# GO-RGO_BOARD_26-09-22_final_update_7PM.net
KiCad netlist of a schematic drawn in EAGLE
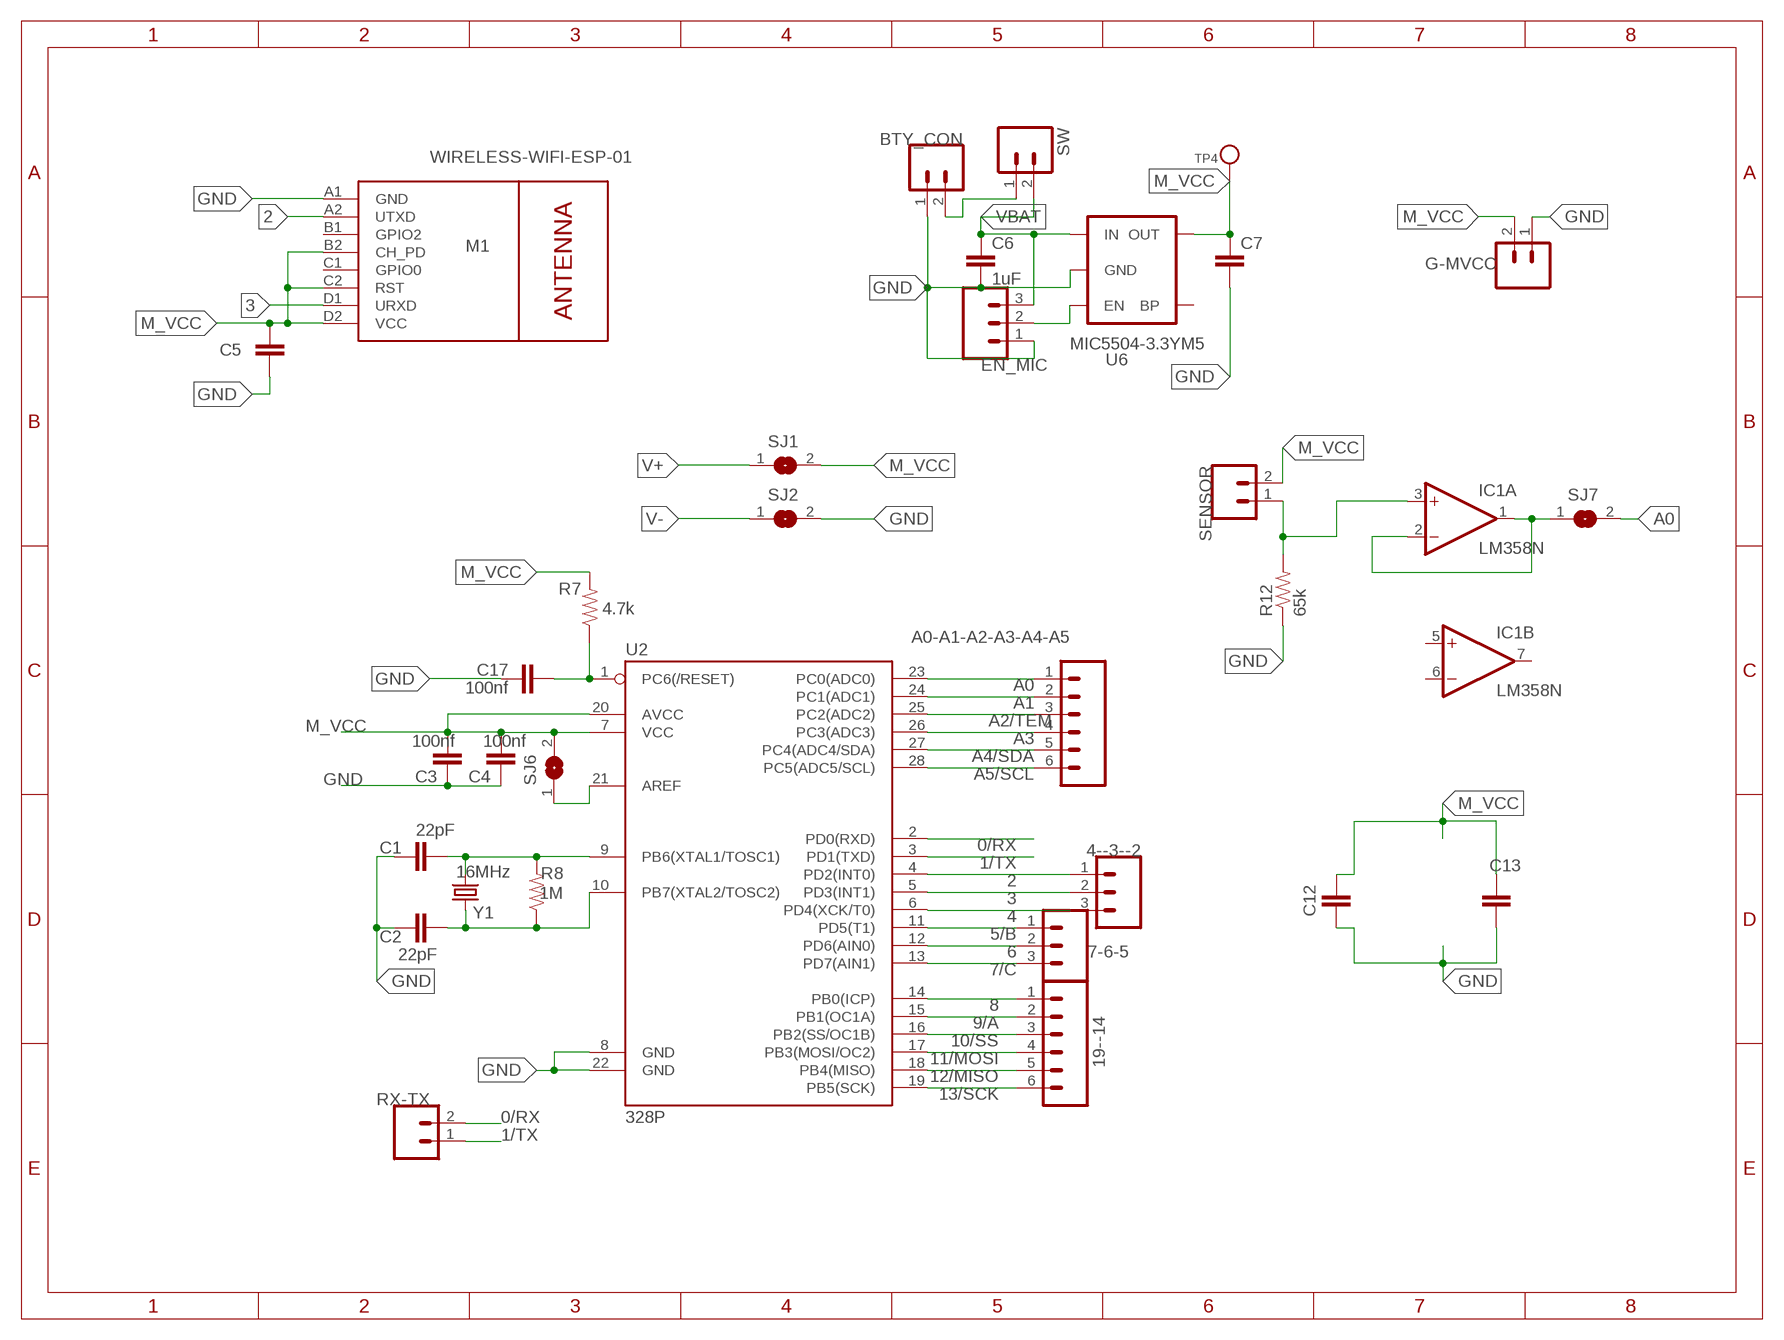
[diagram p0: schematic, sheet 1]

(export (version "E")
  (design (tool "Eeschema 10.0.6"))
  (components
    (comp (ref "4--3--2")
      (value "M03PTH")
      (footprint "eagle-import:1X03")
      (libsource (lib "eagle-import") (part "M03PTH"))
    )
    (comp (ref "7-6-5")
      (value "M03PTH")
      (footprint "eagle-import:1X03")
      (libsource (lib "eagle-import") (part "SparkFun-Connectors1_M03PTH"))
    )
    (comp (ref "19--14")
      (value "M06SIP")
      (footprint "eagle-import:1X06")
      (libsource (lib "eagle-import") (part "M06SIP"))
    )
    (comp (ref "A0-A1-A2-A3-A4-A5")
      (value "M06SIP")
      (footprint "eagle-import:1X06")
      (libsource (lib "eagle-import") (part "M06SIP"))
    )
    (comp (ref "BTY_CON")
      (value "M02PTH")
      (footprint "eagle-import:1X02")
      (libsource (lib "eagle-import") (part "SparkFun-3-2-07_M02PTH"))
    )
    (comp (ref "C1")
      (value "22pF")
      (footprint "eagle-import:0805")
      (libsource (lib "eagle-import") (part "CAP0805"))
    )
    (comp (ref "C2")
      (value "22pF")
      (footprint "eagle-import:0805")
      (libsource (lib "eagle-import") (part "CAP0805"))
    )
    (comp (ref "C3")
      (value "100nf")
      (footprint "eagle-import:0805")
      (libsource (lib "eagle-import") (part "CAP0805"))
    )
    (comp (ref "C4")
      (value "100nf")
      (footprint "eagle-import:0805")
      (libsource (lib "eagle-import") (part "CAP0805"))
    )
    (comp (ref "C5")
      (value "100nf")
      (footprint "eagle-import:0805")
      (libsource (lib "eagle-import") (part "CAP0805"))
    )
    (comp (ref "C6")
      (value "1uF")
      (footprint "eagle-import:0805")
      (libsource (lib "eagle-import") (part "SparkFun-Passives1_CAP0805"))
    )
    (comp (ref "C7")
      (value "1uF")
      (footprint "eagle-import:0805")
      (libsource (lib "eagle-import") (part "SparkFun-Passives1_CAP0805"))
    )
    (comp (ref "C12")
      (value "100nf")
      (footprint "eagle-import:0805")
      (libsource (lib "eagle-import") (part "SparkFun-Passives1_CAP0805"))
    )
    (comp (ref "C13")
      (value "100nf")
      (footprint "eagle-import:0805")
      (libsource (lib "eagle-import") (part "SparkFun-Passives1_CAP0805"))
    )
    (comp (ref "C17")
      (value "100nf")
      (footprint "eagle-import:0805")
      (libsource (lib "eagle-import") (part "CAP0805"))
    )
    (comp (ref "EN_MIC")
      (value "M03PTH")
      (footprint "eagle-import:1X03")
      (libsource (lib "eagle-import") (part "SparkFun-3-2-07_M03PTH"))
    )
    (comp (ref "G-MVCC")
      (value "M02PTH")
      (footprint "eagle-import:1X02")
      (libsource (lib "eagle-import") (part "SparkFun-3-2-07_M02PTH"))
    )
    (comp (ref "IC1")
      (value "LM358N")
      (footprint "eagle-import:DIL08")
      (libsource (lib "eagle-import") (part "LM358N"))
    )
    (comp (ref "M1")
      (value "WIRELESS-WIFI-ESP-01")
      (footprint "eagle-import:WIRELESS-WIFI-ESP-01")
      (libsource (lib "eagle-import") (part "WIRELESS-WIFI-ESP-01"))
    )
    (comp (ref "R7")
      (value "4.7k")
      (footprint "eagle-import:0805")
      (libsource (lib "eagle-import") (part "RESISTOR0805-RES"))
    )
    (comp (ref "R8")
      (value "1M")
      (footprint "eagle-import:0805")
      (libsource (lib "eagle-import") (part "RESISTOR0805-RES"))
    )
    (comp (ref "R12")
      (value "65k")
      (footprint "eagle-import:0805")
      (libsource (lib "eagle-import") (part "RESISTOR0805-RES"))
    )
    (comp (ref "RX-TX")
      (value "M02PTH")
      (footprint "eagle-import:1X02")
      (libsource (lib "eagle-import") (part "SparkFun-3-2-07_M02PTH"))
    )
    (comp (ref "SENSOR")
      (value "M02PTH")
      (footprint "eagle-import:1X02")
      (libsource (lib "eagle-import") (part "SparkFun-3-2-07_M02PTH"))
    )
    (comp (ref "SJ1") (value "SJ") (footprint "eagle-import:SJ") (libsource (lib "eagle-import") (part "SJ")))
    (comp (ref "SJ2") (value "SJ") (footprint "eagle-import:SJ") (libsource (lib "eagle-import") (part "SJ")))
    (comp (ref "SJ6") (value "SJ") (footprint "eagle-import:SJ") (libsource (lib "eagle-import") (part "SJ")))
    (comp (ref "SJ7") (value "SJ") (footprint "eagle-import:SJ") (libsource (lib "eagle-import") (part "SJ")))
    (comp (ref "SW")
      (value "M02PTH")
      (footprint "eagle-import:1X02")
      (libsource (lib "eagle-import") (part "M02PTH"))
    )
    (comp (ref "TP4")
      (value "TESTPOINTROUND1MM")
      (footprint "eagle-import:TESTPOINT_ROUND_1MM")
      (libsource (lib "eagle-import") (part "TESTPOINTROUND1MM"))
    )
    (comp (ref "U2")
      (value "328P")
      (footprint "eagle-import:DIP28")
      (libsource (lib "eagle-import") (part "ATMEGA328P_PDIP"))
    )
    (comp (ref "U6")
      (value "MIC5504-3.3YM5")
      (footprint "eagle-import:SOT23-5")
      (libsource (lib "eagle-import") (part "V_REG_LDOSMD"))
    )
    (comp (ref "Y1")
      (value "16MHz")
      (footprint "eagle-import:HC49US")
      (libsource (lib "eagle-import") (part "CRYSTAL-16MHZPTH-HC49US"))
    )
  )
  (nets
    (net (code "1") (name "/0{slash}RX") (class "Default")
      (node (ref "RX-TX") (pin "2") (pinfunction "2_2") (pintype "passive"))
      (node (ref "U2") (pin "2") (pinfunction "PD0(RXD)_2") (pintype "bidirectional"))
    )
    (net (code "2") (name "/1{slash}TX") (class "Default")
      (node (ref "RX-TX") (pin "1") (pinfunction "1_1") (pintype "passive"))
      (node (ref "U2") (pin "3") (pinfunction "PD1(TXD)_3") (pintype "bidirectional"))
    )
    (net (code "3") (name "/4") (class "Default")
      (node (ref "4--3--2") (pin "3") (pinfunction "3_3") (pintype "passive"))
      (node (ref "U2") (pin "6") (pinfunction "PD4(XCK/T0)_6") (pintype "bidirectional"))
    )
    (net (code "4") (name "/5{slash}B") (class "Default")
      (node (ref "7-6-5") (pin "1") (pinfunction "1_1") (pintype "passive"))
      (node (ref "U2") (pin "11") (pinfunction "PD5(T1)_11") (pintype "bidirectional"))
    )
    (net (code "5") (name "/6") (class "Default")
      (node (ref "7-6-5") (pin "2") (pinfunction "2_2") (pintype "passive"))
      (node (ref "U2") (pin "12") (pinfunction "PD6(AIN0)_12") (pintype "bidirectional"))
    )
    (net (code "6") (name "/7{slash}C") (class "Default")
      (node (ref "7-6-5") (pin "3") (pinfunction "3_3") (pintype "passive"))
      (node (ref "U2") (pin "13") (pinfunction "PD7(AIN1)_13") (pintype "bidirectional"))
    )
    (net (code "7") (name "/8") (class "Default")
      (node (ref "19--14") (pin "1") (pinfunction "1_1") (pintype "passive"))
      (node (ref "U2") (pin "14") (pinfunction "PB0(ICP)_14") (pintype "bidirectional"))
    )
    (net (code "8") (name "/9{slash}A") (class "Default")
      (node (ref "19--14") (pin "2") (pinfunction "2_2") (pintype "passive"))
      (node (ref "U2") (pin "15") (pinfunction "PB1(OC1A)_15") (pintype "bidirectional"))
    )
    (net (code "9") (name "/10{slash}SS") (class "Default")
      (node (ref "19--14") (pin "3") (pinfunction "3_3") (pintype "passive"))
      (node (ref "U2") (pin "16") (pinfunction "PB2(SS/OC1B)_16") (pintype "bidirectional"))
    )
    (net (code "10") (name "/11{slash}MOSI") (class "Default")
      (node (ref "19--14") (pin "4") (pinfunction "4_4") (pintype "passive"))
      (node (ref "U2") (pin "17") (pinfunction "PB3(MOSI/OC2)_17") (pintype "bidirectional"))
    )
    (net (code "11") (name "/12{slash}MISO") (class "Default")
      (node (ref "19--14") (pin "5") (pinfunction "5_5") (pintype "passive"))
      (node (ref "U2") (pin "18") (pinfunction "PB4(MISO)_18") (pintype "bidirectional"))
    )
    (net (code "12") (name "/13{slash}SCK") (class "Default")
      (node (ref "19--14") (pin "6") (pinfunction "6_6") (pintype "passive"))
      (node (ref "U2") (pin "19") (pinfunction "PB5(SCK)_19") (pintype "bidirectional"))
    )
    (net (code "13") (name "/A1") (class "Default")
      (node (ref "A0-A1-A2-A3-A4-A5") (pin "2") (pinfunction "2_2") (pintype "passive"))
      (node (ref "U2") (pin "24") (pinfunction "PC1(ADC1)_24") (pintype "bidirectional"))
    )
    (net (code "14") (name "/A2{slash}TEM") (class "Default")
      (node (ref "A0-A1-A2-A3-A4-A5") (pin "3") (pinfunction "3_3") (pintype "passive"))
      (node (ref "U2") (pin "25") (pinfunction "PC2(ADC2)_25") (pintype "bidirectional"))
    )
    (net (code "15") (name "/A3") (class "Default")
      (node (ref "A0-A1-A2-A3-A4-A5") (pin "4") (pinfunction "4_4") (pintype "passive"))
      (node (ref "U2") (pin "26") (pinfunction "PC3(ADC3)_26") (pintype "bidirectional"))
    )
    (net (code "16") (name "/A4{slash}SDA") (class "Default")
      (node (ref "A0-A1-A2-A3-A4-A5") (pin "5") (pinfunction "5_5") (pintype "passive"))
      (node (ref "U2") (pin "27") (pinfunction "PC4(ADC4/SDA)_27") (pintype "bidirectional"))
    )
    (net (code "17") (name "/A5{slash}SCL") (class "Default")
      (node (ref "A0-A1-A2-A3-A4-A5") (pin "6") (pinfunction "6_6") (pintype "passive"))
      (node (ref "U2") (pin "28") (pinfunction "PC5(ADC5/SCL)_28") (pintype "bidirectional"))
    )
    (net (code "18") (name "2") (class "Default")
      (node (ref "4--3--2") (pin "1") (pinfunction "1_1") (pintype "passive"))
      (node (ref "M1") (pin "A2") (pinfunction "UTXD_A2") (pintype "bidirectional"))
      (node (ref "U2") (pin "4") (pinfunction "PD2(INT0)_4") (pintype "bidirectional"))
    )
    (net (code "19") (name "3") (class "Default")
      (node (ref "4--3--2") (pin "2") (pinfunction "2_2") (pintype "passive"))
      (node (ref "M1") (pin "D1") (pinfunction "URXD_D1") (pintype "bidirectional"))
      (node (ref "U2") (pin "5") (pinfunction "PD3(INT1)_5") (pintype "bidirectional"))
    )
    (net (code "20") (name "A0") (class "Default")
      (node (ref "A0-A1-A2-A3-A4-A5") (pin "1") (pinfunction "1_1") (pintype "passive"))
      (node (ref "SJ7") (pin "2") (pinfunction "2_2") (pintype "passive"))
      (node (ref "U2") (pin "23") (pinfunction "PC0(ADC0)_23") (pintype "bidirectional"))
    )
    (net (code "21") (name "GND") (class "Default")
      (node (ref "BTY_CON") (pin "1") (pinfunction "1_1") (pintype "passive"))
      (node (ref "C1") (pin "1") (pinfunction "1_1") (pintype "passive"))
      (node (ref "C12") (pin "1") (pinfunction "1_1") (pintype "passive"))
      (node (ref "C13") (pin "1") (pinfunction "1_1") (pintype "passive"))
      (node (ref "C17") (pin "1") (pinfunction "1_1") (pintype "passive"))
      (node (ref "C2") (pin "1") (pinfunction "1_1") (pintype "passive"))
      (node (ref "C3") (pin "1") (pinfunction "1_1") (pintype "passive"))
      (node (ref "C4") (pin "1") (pinfunction "1_1") (pintype "passive"))
      (node (ref "C5") (pin "1") (pinfunction "1_1") (pintype "passive"))
      (node (ref "C6") (pin "2") (pinfunction "2_2") (pintype "passive"))
      (node (ref "C7") (pin "2") (pinfunction "2_2") (pintype "passive"))
      (node (ref "EN_MIC") (pin "1") (pinfunction "1_1") (pintype "passive"))
      (node (ref "G-MVCC") (pin "1") (pinfunction "1_1") (pintype "passive"))
      (node (ref "M1") (pin "A1") (pinfunction "GND_A1") (pintype "power_in"))
      (node (ref "R12") (pin "1") (pinfunction "1_1") (pintype "passive"))
      (node (ref "SJ2") (pin "2") (pinfunction "2_2") (pintype "passive"))
      (node (ref "U2") (pin "22") (pinfunction "GND_22") (pintype "bidirectional"))
      (node (ref "U2") (pin "8") (pinfunction "GND_8") (pintype "bidirectional"))
      (node (ref "U6") (pin "2") (pinfunction "GND_2") (pintype "input"))
    )
    (net (code "22") (name "M_VCC") (class "Default")
      (node (ref "C12") (pin "2") (pinfunction "2_2") (pintype "passive"))
      (node (ref "C13") (pin "2") (pinfunction "2_2") (pintype "passive"))
      (node (ref "C3") (pin "2") (pinfunction "2_2") (pintype "passive"))
      (node (ref "C4") (pin "2") (pinfunction "2_2") (pintype "passive"))
      (node (ref "C5") (pin "2") (pinfunction "2_2") (pintype "passive"))
      (node (ref "C7") (pin "1") (pinfunction "1_1") (pintype "passive"))
      (node (ref "G-MVCC") (pin "2") (pinfunction "2_2") (pintype "passive"))
      (node (ref "M1") (pin "B2") (pinfunction "CH_PD_B2") (pintype "bidirectional"))
      (node (ref "M1") (pin "C2") (pinfunction "RST_C2") (pintype "bidirectional"))
      (node (ref "M1") (pin "D2") (pinfunction "VCC_D2") (pintype "power_in"))
      (node (ref "R7") (pin "2") (pinfunction "2_2") (pintype "passive"))
      (node (ref "SENSOR") (pin "2") (pinfunction "2_2") (pintype "passive"))
      (node (ref "SJ1") (pin "2") (pinfunction "2_2") (pintype "passive"))
      (node (ref "SJ6") (pin "2") (pinfunction "2_2") (pintype "passive"))
      (node (ref "TP4") (pin "P$1") (pinfunction "P$1_P$1") (pintype "bidirectional"))
      (node (ref "U2") (pin "20") (pinfunction "AVCC_20") (pintype "bidirectional"))
      (node (ref "U2") (pin "7") (pinfunction "VCC_7") (pintype "bidirectional"))
      (node (ref "U6") (pin "5") (pinfunction "OUT_5") (pintype "passive"))
    )
    (net (code "23") (name "Net-(BTY_CON-Pad2)") (class "Default")
      (node (ref "BTY_CON") (pin "2") (pinfunction "2_2") (pintype "passive"))
      (node (ref "SW") (pin "1") (pinfunction "1_1") (pintype "passive"))
    )
    (net (code "24") (name "Net-(IC1A-+IN)") (class "Default")
      (node (ref "IC1") (pin "3") (pinfunction "+IN_3") (pintype "input"))
      (node (ref "R12") (pin "2") (pinfunction "2_2") (pintype "passive"))
      (node (ref "SENSOR") (pin "1") (pinfunction "1_1") (pintype "passive"))
    )
    (net (code "25") (name "Net-(IC1A--IN)") (class "Default")
      (node (ref "IC1") (pin "1") (pinfunction "OUT_1") (pintype "output"))
      (node (ref "IC1") (pin "2") (pinfunction "-IN_2") (pintype "input"))
      (node (ref "SJ7") (pin "1") (pinfunction "1_1") (pintype "passive"))
    )
    (net (code "26") (name "Net-(U2-AREF)") (class "Default")
      (node (ref "SJ6") (pin "1") (pinfunction "1_1") (pintype "passive"))
      (node (ref "U2") (pin "21") (pinfunction "AREF_21") (pintype "bidirectional"))
    )
    (net (code "27") (name "Net-(U2-PB6(XTAL1{slash}TOSC1))") (class "Default")
      (node (ref "C1") (pin "2") (pinfunction "2_2") (pintype "passive"))
      (node (ref "R8") (pin "2") (pinfunction "2_2") (pintype "passive"))
      (node (ref "U2") (pin "9") (pinfunction "PB6(XTAL1/TOSC1)_9") (pintype "bidirectional"))
      (node (ref "Y1") (pin "2") (pinfunction "2_2") (pintype "passive"))
    )
    (net (code "28") (name "Net-(U2-PB7(XTAL2{slash}TOSC2))") (class "Default")
      (node (ref "C2") (pin "2") (pinfunction "2_2") (pintype "passive"))
      (node (ref "R8") (pin "1") (pinfunction "1_1") (pintype "passive"))
      (node (ref "U2") (pin "10") (pinfunction "PB7(XTAL2/TOSC2)_10") (pintype "bidirectional"))
      (node (ref "Y1") (pin "1") (pinfunction "1_1") (pintype "passive"))
    )
    (net (code "29") (name "Net-(U2-PC6({slash}RESET))") (class "Default")
      (node (ref "C17") (pin "2") (pinfunction "2_2") (pintype "passive"))
      (node (ref "R7") (pin "1") (pinfunction "1_1") (pintype "passive"))
      (node (ref "U2") (pin "1") (pinfunction "PC6(/RESET)_1") (pintype "bidirectional"))
    )
    (net (code "30") (name "Net-(U6-EN)") (class "Default")
      (node (ref "EN_MIC") (pin "2") (pinfunction "2_2") (pintype "passive"))
      (node (ref "U6") (pin "3") (pinfunction "EN_3") (pintype "input"))
    )
    (net (code "31") (name "V+") (class "Default")
      (node (ref "SJ1") (pin "1") (pinfunction "1_1") (pintype "passive"))
    )
    (net (code "32") (name "V-") (class "Default")
      (node (ref "SJ2") (pin "1") (pinfunction "1_1") (pintype "passive"))
    )
    (net (code "33") (name "VBAT") (class "Default")
      (node (ref "C6") (pin "1") (pinfunction "1_1") (pintype "passive"))
      (node (ref "EN_MIC") (pin "3") (pinfunction "3_3") (pintype "passive"))
      (node (ref "SW") (pin "2") (pinfunction "2_2") (pintype "passive"))
      (node (ref "U6") (pin "1") (pinfunction "IN_1") (pintype "input"))
    )
    (net (code "34") (name "unconnected-(IC1B-+IN-Pad5)") (class "Default")
      (node (ref "IC1") (pin "5") (pinfunction "+IN_5") (pintype "input"))
    )
    (net (code "35") (name "unconnected-(IC1B--IN-Pad6)") (class "Default")
      (node (ref "IC1") (pin "6") (pinfunction "-IN_6") (pintype "input"))
    )
    (net (code "36") (name "unconnected-(IC1B-OUT-Pad7)") (class "Default")
      (node (ref "IC1") (pin "7") (pinfunction "OUT_7") (pintype "output"))
    )
    (net (code "37") (name "unconnected-(M1-GPIO0-PadC1)") (class "Default")
      (node (ref "M1") (pin "C1") (pinfunction "GPIO0_C1") (pintype "bidirectional"))
    )
    (net (code "38") (name "unconnected-(M1-GPIO2-PadB1)") (class "Default")
      (node (ref "M1") (pin "B1") (pinfunction "GPIO2_B1") (pintype "bidirectional"))
    )
    (net (code "39") (name "unconnected-(U6-BP-Pad4)") (class "Default")
      (node (ref "U6") (pin "4") (pinfunction "BP_4") (pintype "input"))
    )
  )
)
